# Fuse.net
KiCad netlist of a schematic drawn in Altium Designer
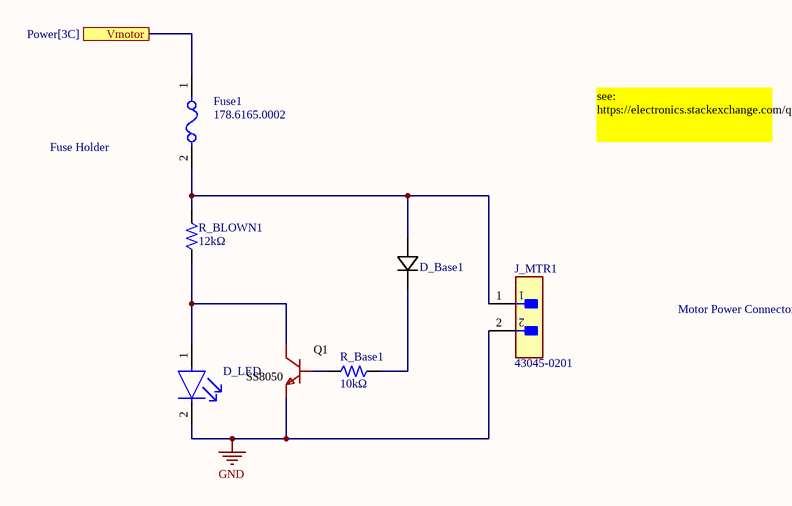
[diagram p0: Fuse.SchDoc]

(export (version "E")
  (design (tool "Eeschema 10.0.6"))
  (components
    (comp (ref "D_Base1")
      (value "Diode")
      (footprint "M7:M7_MDD")
      (description "1A Independent Type 1kV 1.1V@1A SMA(DO-214AC) Diodes - General Purpose ROHS")
      (libsource (lib "M7") (part "M7"))
    )
    (comp (ref "D_LED")
      (value "~")
      (footprint "FP-AP2012EC-MFG")
      (description "LED RED CLEAR SMD")
      (libsource (lib "Red-LED - 01.02.26 - 14") (part "ab1c01a81903e929fc6c44469aada92"))
    )
    (comp (ref "Fuse1")
      (value "178.6165.0002")
      (footprint "FP-178_6165-MFG")
      (description "FUSE HOLDER BLADE 80V PCB")
      (fields
        (field (name "MANUFACTURER") "Littelfuse")
        (field (name "OCTOPART") "https://octopart.com/178.6165.0002-littelfuse-13138759")
      )
      (libsource (lib "Altium Content Vault") (part "5bcf9b9f640e542cf0359d10258e979"))
    )
    (comp (ref "J_MTR1")
      (value "43045-0201")
      (footprint "FP-43045-0201-MFG")
      (description "CONN HEADER R/A 2POS")
      (libsource (lib "Altium Content Vault") (part "3bc925449376181038e59eaffc5286c"))
    )
    (comp (ref "Q1")
      (value "SS8050")
      (footprint "SOT-23-3_L2.9-W1.3-P1.90-LS2.4-BR")
      (description "BJT NPN")
      (fields
        (field (name "MANUFACTURER") "CJ(江苏长电/长晶)")
        (field (name "MANUFACTURER PART") "SS8050(RANGE:200-350)")
      )
      (libsource (lib "SS8050_C21501_SS8050_C2150") (part "SS8050(RANGE{colon}200-350)_C2150"))
    )
    (comp (ref "R_Base1")
      (value "0603WAF1002T5E")
      (footprint "RES-0603")
      (description "Resistor, 10kΩ, ±1%, 100mW, 75V, ±100ppm/℃, -55℃~+155℃, SMD 0603")
      (fields
        (field (name "MANUFACTURER") "Uniroyal")
        (field (name "JLCPCB PART NUMBER") "C25804")
        (field (name "RESISTANCE") "10kΩ")
      )
      (libsource (lib "jlcpcb_2024_10_resistors_basic") (part "0603WAF1002T5E"))
    )
    (comp (ref "R_BLOWN1")
      (value "0402WGF1202TCE")
      (footprint "RES-0402")
      (description "Resistor, 12kΩ, ±1%, 62.5mW, 50V, ±100ppm/℃, -55℃~+155℃, SMD 0402")
      (fields
        (field (name "MANUFACTURER") "Uniroyal")
        (field (name "JLCPCB PART NUMBER") "C25752")
        (field (name "RESISTANCE") "12kΩ")
      )
      (libsource (lib "jlcpcb_2024_10_resistors_basic") (part "0402WGF1202TCE"))
    )
  )
  (nets
    (net (code "1") (name "/Vmotor") (class "Default")
      (node (ref "Fuse1") (pin "1") (pinfunction "1_1") (pintype "passive"))
    )
    (net (code "2") (name "GND") (class "Default")
      (node (ref "D_LED") (pin "2") (pinfunction "C_2") (pintype "passive"))
      (node (ref "J_MTR1") (pin "2") (pinfunction "2_2") (pintype "passive"))
      (node (ref "Q1") (pin "2") (pinfunction "E_2") (pintype "passive"))
    )
    (net (code "3") (name "Net-(D_Base1-ANODE)") (class "Default")
      (node (ref "D_Base1") (pin "2") (pinfunction "ANODE_2") (pintype "passive"))
      (node (ref "Fuse1") (pin "2") (pinfunction "2_2") (pintype "passive"))
      (node (ref "J_MTR1") (pin "1") (pinfunction "1_1") (pintype "passive"))
      (node (ref "R_BLOWN1") (pin "2") (pinfunction "2_2") (pintype "passive"))
    )
    (net (code "4") (name "Net-(D_Base1-CATHODE)") (class "Default")
      (node (ref "D_Base1") (pin "1") (pinfunction "CATHODE_1") (pintype "passive"))
      (node (ref "R_Base1") (pin "2") (pinfunction "2_2") (pintype "passive"))
    )
    (net (code "5") (name "Net-(D_LED-A)") (class "Default")
      (node (ref "D_LED") (pin "1") (pinfunction "A_1") (pintype "passive"))
      (node (ref "Q1") (pin "3") (pinfunction "C_3") (pintype "passive"))
      (node (ref "R_BLOWN1") (pin "1") (pinfunction "1_1") (pintype "passive"))
    )
    (net (code "6") (name "Net-(Q1-B)") (class "Default")
      (node (ref "Q1") (pin "1") (pinfunction "B_1") (pintype "passive"))
      (node (ref "R_Base1") (pin "1") (pinfunction "1_1") (pintype "passive"))
    )
  )
)
